# UNO-TH_Rev3e.net
KiCad netlist of a schematic drawn in Altium Designer
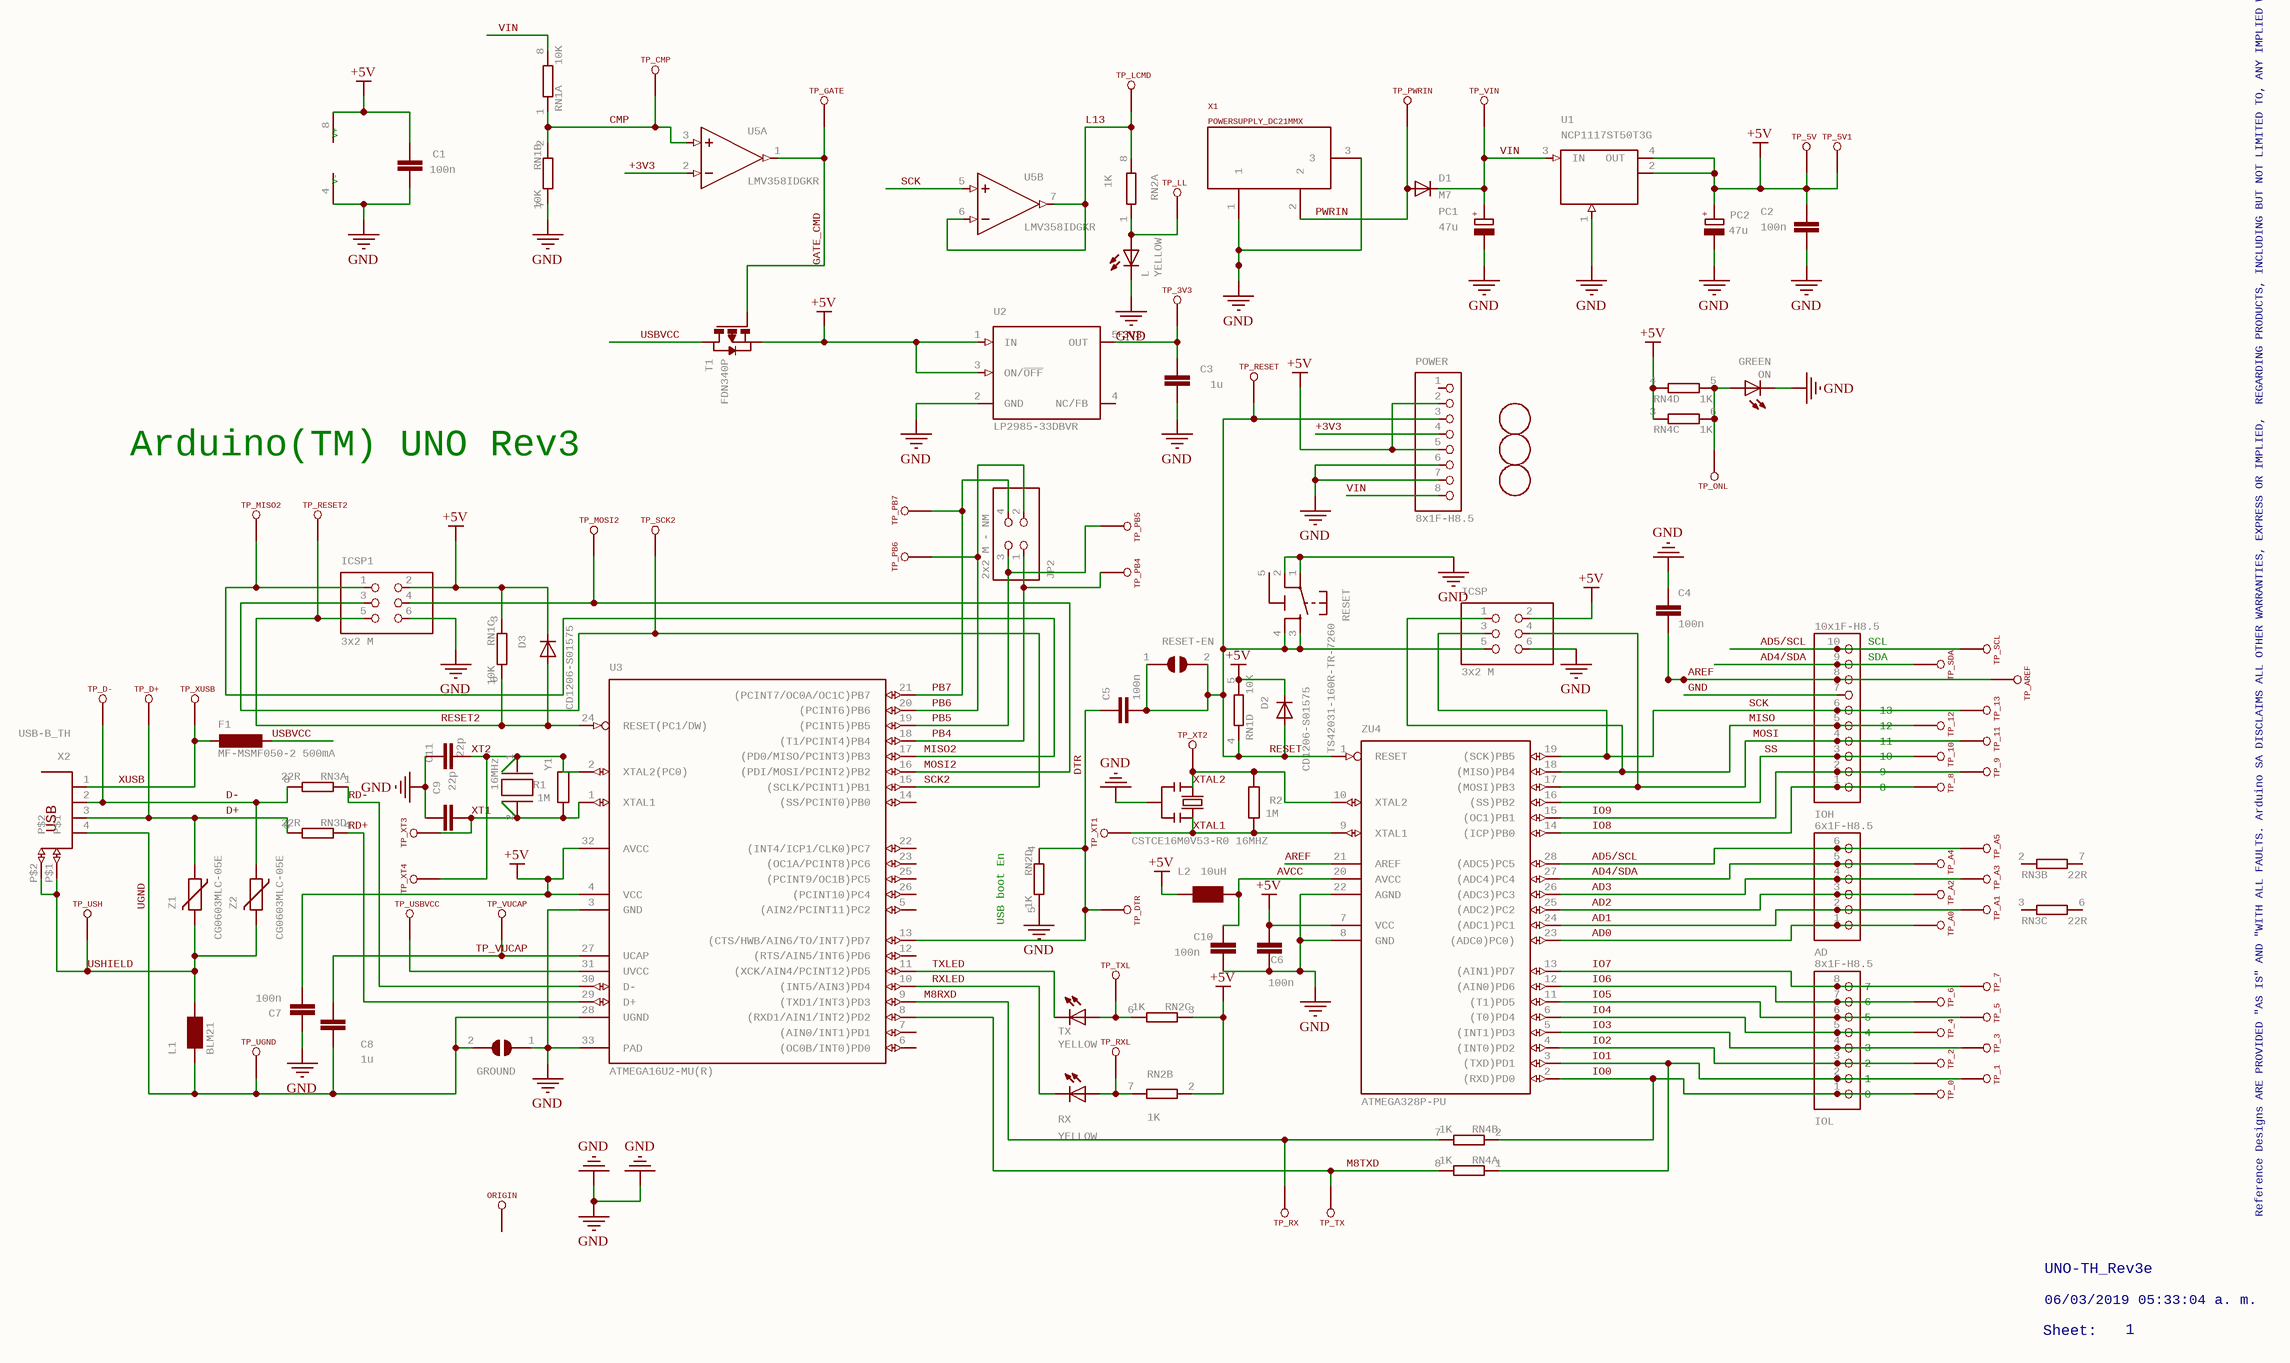
[diagram p0: UNO-TH_Rev3e.SchDoc]

(export (version "E")
  (design (tool "Eeschema 10.0.6"))
  (components
    (comp (ref "AD")
      (value "6x1F-H8.5")
      (footprint "1X06")
      (description "PIN HEADER")
      (libsource (lib "SmartPrj") (part "PINHD-1X6"))
    )
    (comp (ref "C1")
      (value "100n")
      (footprint "C0603-ROUND")
      (description "CAPACITOR, European symbol")
      (libsource (lib "") (part "C-EU0603-RND_1"))
    )
    (comp (ref "C2")
      (value "100n")
      (footprint "C0603-ROUND")
      (description "CAPACITOR, European symbol")
      (libsource (lib "") (part "C-EU0603-RND_3"))
    )
    (comp (ref "C3")
      (value "1u")
      (footprint "C0603-ROUND")
      (description "CAPACITOR, European symbol")
      (libsource (lib "") (part "C-EU0603-RND_1"))
    )
    (comp (ref "C4")
      (value "100n")
      (footprint "C0603-ROUND")
      (description "CAPACITOR, European symbol")
      (libsource (lib "") (part "C-EU0603-RND_2"))
    )
    (comp (ref "C5")
      (value "100n")
      (footprint "C0603-ROUND")
      (description "CAPACITOR, European symbol")
      (libsource (lib "") (part "C-EU0603-RND_1"))
    )
    (comp (ref "C6")
      (value "100n")
      (footprint "C0603-ROUND")
      (description "CAPACITOR, European symbol")
      (libsource (lib "") (part "C-EU0603-RND_3"))
    )
    (comp (ref "C7")
      (value "100n")
      (footprint "C0603-ROUND")
      (description "CAPACITOR, European symbol")
      (libsource (lib "SmartPrj") (part "C-EU0603-RND"))
    )
    (comp (ref "C8")
      (value "1u")
      (footprint "C0603-ROUND")
      (description "CAPACITOR, European symbol")
      (libsource (lib "SmartPrj") (part "C-EU0603-RND"))
    )
    (comp (ref "C9")
      (value "22p")
      (footprint "C0603-ROUND")
      (description "CAPACITOR, European symbol")
      (libsource (lib "") (part "C-EU0603-RND_2"))
    )
    (comp (ref "C10")
      (value "100n")
      (footprint "C0603-ROUND")
      (description "CAPACITOR, European symbol")
      (libsource (lib "") (part "C-EU0603-RND_3"))
    )
    (comp (ref "C11")
      (value "22p")
      (footprint "C0603-ROUND")
      (description "CAPACITOR, European symbol")
      (libsource (lib "") (part "C-EU0603-RND_2"))
    )
    (comp (ref "D1")
      (value "M7")
      (footprint "SMB")
      (description "DIODE")
      (libsource (lib "diode") (part "DIODE-SMB"))
    )
    (comp (ref "D2")
      (value "CD1206-S01575")
      (footprint "MINIMELF")
      (description "DIODE")
      (libsource (lib "diode") (part "DIODE-MINIMELF"))
    )
    (comp (ref "D3")
      (value "CD1206-S01575")
      (footprint "MINIMELF")
      (description "DIODE")
      (libsource (lib "diode") (part "DIODE-MINIMELF"))
    )
    (comp (ref "F1")
      (value "MF-MSMF050-2 500mA")
      (footprint "L1812")
      (description "INDUCTOR, European symbol")
      (libsource (lib "rcl") (part "L-EUL1812"))
    )
    (comp (ref "FD1")
      (value "FIDUCIALMOUNT")
      (footprint "FIDUCIA-MOUNT")
      (libsource (lib "SmartPrj") (part "FIDUCIALMOUNT"))
    )
    (comp (ref "FD2")
      (value "FIDUCIALMOUNT")
      (footprint "FIDUCIA-MOUNT")
      (libsource (lib "SmartPrj") (part "FIDUCIALMOUNT"))
    )
    (comp (ref "FD3")
      (value "FIDUCIALMOUNT")
      (footprint "FIDUCIA-MOUNT")
      (libsource (lib "SmartPrj") (part "FIDUCIALMOUNT"))
    )
    (comp (ref "GROUND")
      (value "SJ")
      (footprint "SJ")
      (description "SMD solder JUMPER")
      (libsource (lib "jumper") (part "SJ"))
    )
    (comp (ref "ICSP")
      (value "3x2 M")
      (footprint "2X03")
      (description "PIN HEADER")
      (libsource (lib "SmartPrj") (part "PINHD-2X3"))
    )
    (comp (ref "ICSP1")
      (value "3x2 M")
      (footprint "2X03")
      (description "PIN HEADER")
      (libsource (lib "SmartPrj") (part "PINHD-2X3"))
    )
    (comp (ref "IOH")
      (value "10x1F-H8.5")
      (footprint "1X10")
      (description "PIN HEADER")
      (libsource (lib "SmartPrj") (part "PINHD-1X10_ARD"))
    )
    (comp (ref "IOL")
      (value "8x1F-H8.5")
      (footprint "1X08")
      (description "PIN HEADER")
      (libsource (lib "SmartPrj") (part "PINHD-1X8"))
    )
    (comp (ref "JP2")
      (value "2x2 M - NM")
      (footprint "2X02")
      (description "PIN HEADER")
      (libsource (lib "SmartPrj") (part "PINHD-2X2"))
    )
    (comp (ref "L")
      (value "YELLOW")
      (footprint "CHIP-LED0805")
      (libsource (lib "led") (part "LEDCHIP-LED0805"))
    )
    (comp (ref "L1")
      (value "BLM21")
      (footprint "0805")
      (libsource (lib "wuerth-elektronik") (part "WE-CBF_0805"))
    )
    (comp (ref "L2")
      (value "10uH")
      (footprint "0805")
      (description "10uH 0805")
      (fields (field (name "PART_NUMBER") "CV201210-100K"))
      (libsource (lib "Induttanze") (part "0715_CV201210-100K"))
    )
    (comp (ref "ON")
      (value "GREEN")
      (footprint "CHIP-LED0805")
      (libsource (lib "led") (part "LEDCHIP-LED0805"))
    )
    (comp (ref "ORIGIN") (value "TP_SP") (footprint "TP-SP") (libsource (lib "SmartPrj") (part "TP_SP")))
    (comp (ref "PC1")
      (value "47u")
      (footprint "PANASONIC_D")
      (description "POLARIZED CAPACITOR, European symbol")
      (fields (field (name "+") "+"))
      (libsource (lib "rcl") (part "CPOL-EUD"))
    )
    (comp (ref "PC2")
      (value "47u")
      (footprint "PANASONIC_D")
      (description "POLARIZED CAPACITOR, European symbol")
      (fields (field (name "+") "+"))
      (libsource (lib "rcl") (part "CPOL-EUD"))
    )
    (comp (ref "POWER")
      (value "8x1F-H8.5")
      (footprint "1X08")
      (description "PIN HEADER")
      (libsource (lib "SmartPrj") (part "PINHD-1X8"))
    )
    (comp (ref "R1")
      (value "1M")
      (footprint "R0603-ROUND")
      (description "RESISTOR, European symbol")
      (libsource (lib "SmartPrj") (part "R-EU_R0603"))
    )
    (comp (ref "R2")
      (value "1M")
      (footprint "R0603-ROUND")
      (description "RESISTOR, European symbol")
      (libsource (lib "SmartPrj") (part "R-EU_R0603"))
    )
    (comp (ref "RESET")
      (value "TS42031-160R-TR-7260")
      (footprint "TS42")
      (description "TS42 Dongnan Electronics Tact switch VDC 12V - 50mA")
      (libsource (lib "SmartPrj") (part "TS42"))
    )
    (comp (ref "RESET-EN")
      (value "SJ")
      (footprint "SJ")
      (description "SMD solder JUMPER")
      (libsource (lib "jumper") (part "SJ"))
    )
    (comp (ref "RN1")
      (value "10K")
      (footprint "CAY16")
      (description "Array Chip Resistor   Source: RS Component / Phycomp")
      (libsource (lib "resistor-dil") (part "4R-NCAY16"))
    )
    (comp (ref "RN2")
      (value "1K")
      (footprint "CAY16")
      (description "Array Chip Resistor   Source: RS Component / Phycomp")
      (libsource (lib "resistor-dil") (part "4R-NCAY16"))
    )
    (comp (ref "RN3")
      (value "22R")
      (footprint "CAY16")
      (description "Array Chip Resistor   Source: RS Component / Phycomp")
      (libsource (lib "resistor-dil") (part "4R-NCAY16"))
    )
    (comp (ref "RN4")
      (value "1K")
      (footprint "CAY16")
      (description "Array Chip Resistor   Source: RS Component / Phycomp")
      (libsource (lib "resistor-dil") (part "4R-NCAY16"))
    )
    (comp (ref "RX")
      (value "YELLOW")
      (footprint "CHIP-LED0805")
      (libsource (lib "led") (part "LEDCHIP-LED0805"))
    )
    (comp (ref "T1")
      (value "FDN340P")
      (footprint "SOT-23")
      (description "MOS FET")
      (libsource (lib "zetex") (part "PMOSSOT23"))
    )
    (comp (ref "TP_0") (value "TP_SP") (footprint "TP-SP") (libsource (lib "SmartPrj") (part "TP_SP")))
    (comp (ref "TP_1") (value "TP_SP") (footprint "TP-SP") (libsource (lib "SmartPrj") (part "TP_SP")))
    (comp (ref "TP_2") (value "TP_SP") (footprint "TP-SP") (libsource (lib "SmartPrj") (part "TP_SP")))
    (comp (ref "TP_3") (value "TP_SP") (footprint "TP-SP") (libsource (lib "SmartPrj") (part "TP_SP")))
    (comp (ref "TP_3V3") (value "TP_SP") (footprint "TP-SP") (libsource (lib "SmartPrj") (part "TP_SP")))
    (comp (ref "TP_4") (value "TP_SP") (footprint "TP-SP") (libsource (lib "SmartPrj") (part "TP_SP")))
    (comp (ref "TP_5") (value "TP_SP") (footprint "TP-SP") (libsource (lib "SmartPrj") (part "TP_SP")))
    (comp (ref "TP_5V") (value "TP_SP") (footprint "TP-SP") (libsource (lib "SmartPrj") (part "TP_SP")))
    (comp (ref "TP_5V1") (value "TP_SP") (footprint "TP-SP") (libsource (lib "SmartPrj") (part "TP_SP")))
    (comp (ref "TP_6") (value "TP_SP") (footprint "TP-SP") (libsource (lib "SmartPrj") (part "TP_SP")))
    (comp (ref "TP_7") (value "TP_SP") (footprint "TP-SP") (libsource (lib "SmartPrj") (part "TP_SP")))
    (comp (ref "TP_8") (value "TP_SP") (footprint "TP-SP") (libsource (lib "SmartPrj") (part "TP_SP")))
    (comp (ref "TP_9") (value "TP_SP") (footprint "TP-SP") (libsource (lib "SmartPrj") (part "TP_SP")))
    (comp (ref "TP_10") (value "TP_SP") (footprint "TP-SP") (libsource (lib "SmartPrj") (part "TP_SP")))
    (comp (ref "TP_11") (value "TP_SP") (footprint "TP-SP") (libsource (lib "SmartPrj") (part "TP_SP")))
    (comp (ref "TP_12") (value "TP_SP") (footprint "TP-SP") (libsource (lib "SmartPrj") (part "TP_SP")))
    (comp (ref "TP_13") (value "TP_SP") (footprint "TP-SP") (libsource (lib "SmartPrj") (part "TP_SP")))
    (comp (ref "TP_A0") (value "TP_SP") (footprint "TP-SP") (libsource (lib "SmartPrj") (part "TP_SP")))
    (comp (ref "TP_A1") (value "TP_SP") (footprint "TP-SP") (libsource (lib "SmartPrj") (part "TP_SP")))
    (comp (ref "TP_A2") (value "TP_SP") (footprint "TP-SP") (libsource (lib "SmartPrj") (part "TP_SP")))
    (comp (ref "TP_A3") (value "TP_SP") (footprint "TP-SP") (libsource (lib "SmartPrj") (part "TP_SP")))
    (comp (ref "TP_A4") (value "TP_SP") (footprint "TP-SP") (libsource (lib "SmartPrj") (part "TP_SP")))
    (comp (ref "TP_A5") (value "TP_SP") (footprint "TP-SP") (libsource (lib "SmartPrj") (part "TP_SP")))
    (comp (ref "TP_AREF") (value "TP_SP") (footprint "TP-SP") (libsource (lib "SmartPrj") (part "TP_SP")))
    (comp (ref "TP_CMP") (value "TP_SP") (footprint "TP-SP") (libsource (lib "SmartPrj") (part "TP_SP")))
    (comp (ref "TP_D+") (value "TP_SP") (footprint "TP-SP") (libsource (lib "SmartPrj") (part "TP_SP")))
    (comp (ref "TP_D-") (value "TP_SP") (footprint "TP-SP") (libsource (lib "SmartPrj") (part "TP_SP")))
    (comp (ref "TP_DTR") (value "TP_SP") (footprint "TP-SP") (libsource (lib "SmartPrj") (part "TP_SP")))
    (comp (ref "TP_GATE") (value "TP_SP") (footprint "TP-SP") (libsource (lib "SmartPrj") (part "TP_SP")))
    (comp (ref "TP_LCMD") (value "TP_SP") (footprint "TP-SP") (libsource (lib "SmartPrj") (part "TP_SP")))
    (comp (ref "TP_LL") (value "TP_SP") (footprint "TP-SP") (libsource (lib "SmartPrj") (part "TP_SP")))
    (comp (ref "TP_MISO2") (value "TP_SP") (footprint "TP-SP") (libsource (lib "SmartPrj") (part "TP_SP")))
    (comp (ref "TP_MOSI2") (value "TP_SP") (footprint "TP-SP") (libsource (lib "SmartPrj") (part "TP_SP")))
    (comp (ref "TP_ONL") (value "TP_SP") (footprint "TP-SP") (libsource (lib "SmartPrj") (part "TP_SP")))
    (comp (ref "TP_PB4") (value "TP_SP") (footprint "TP-SP") (libsource (lib "SmartPrj") (part "TP_SP")))
    (comp (ref "TP_PB5") (value "TP_SP") (footprint "TP-SP") (libsource (lib "SmartPrj") (part "TP_SP")))
    (comp (ref "TP_PB6") (value "TP_SP") (footprint "TP-SP") (libsource (lib "SmartPrj") (part "TP_SP")))
    (comp (ref "TP_PB7") (value "TP_SP") (footprint "TP-SP") (libsource (lib "SmartPrj") (part "TP_SP")))
    (comp (ref "TP_PWRIN") (value "TP_SP") (footprint "TP-SP") (libsource (lib "SmartPrj") (part "TP_SP")))
    (comp (ref "TP_RESET") (value "TP_SP") (footprint "TP-SP") (libsource (lib "SmartPrj") (part "TP_SP")))
    (comp (ref "TP_RESET2") (value "TP_SP") (footprint "TP-SP") (libsource (lib "SmartPrj") (part "TP_SP")))
    (comp (ref "TP_RX") (value "TP_SP") (footprint "TP-SP") (libsource (lib "SmartPrj") (part "TP_SP")))
    (comp (ref "TP_RXL") (value "TP_SP") (footprint "TP-SP") (libsource (lib "SmartPrj") (part "TP_SP")))
    (comp (ref "TP_SCK2") (value "TP_SP") (footprint "TP-SP") (libsource (lib "SmartPrj") (part "TP_SP")))
    (comp (ref "TP_SCL") (value "TP_SP") (footprint "TP-SP") (libsource (lib "SmartPrj") (part "TP_SP")))
    (comp (ref "TP_SDA") (value "TP_SP") (footprint "TP-SP") (libsource (lib "SmartPrj") (part "TP_SP")))
    (comp (ref "TP_TX") (value "TP_SP") (footprint "TP-SP") (libsource (lib "SmartPrj") (part "TP_SP")))
    (comp (ref "TP_TXL") (value "TP_SP") (footprint "TP-SP") (libsource (lib "SmartPrj") (part "TP_SP")))
    (comp (ref "TP_UGND") (value "TP_SP") (footprint "TP-SP") (libsource (lib "SmartPrj") (part "TP_SP")))
    (comp (ref "TP_USBVCC") (value "TP_SP") (footprint "TP-SP") (libsource (lib "SmartPrj") (part "TP_SP")))
    (comp (ref "TP_USH") (value "TP_SP") (footprint "TP-SP") (libsource (lib "SmartPrj") (part "TP_SP")))
    (comp (ref "TP_VIN") (value "TP_SP") (footprint "TP-SP") (libsource (lib "SmartPrj") (part "TP_SP")))
    (comp (ref "TP_VUCAP") (value "TP_SP") (footprint "TP-SP") (libsource (lib "SmartPrj") (part "TP_SP")))
    (comp (ref "TP_XT1") (value "TP_SP") (footprint "TP-SP") (libsource (lib "SmartPrj") (part "TP_SP")))
    (comp (ref "TP_XT2") (value "TP_SP") (footprint "TP-SP") (libsource (lib "SmartPrj") (part "TP_SP")))
    (comp (ref "TP_XT3") (value "TP_SP") (footprint "TP-SP") (libsource (lib "SmartPrj") (part "TP_SP")))
    (comp (ref "TP_XT4") (value "TP_SP") (footprint "TP-SP") (libsource (lib "SmartPrj") (part "TP_SP")))
    (comp (ref "TP_XUSB") (value "TP_SP") (footprint "TP-SP") (libsource (lib "SmartPrj") (part "TP_SP")))
    (comp (ref "TX")
      (value "YELLOW")
      (footprint "CHIP-LED0805")
      (libsource (lib "led") (part "LEDCHIP-LED0805"))
    )
    (comp (ref "U1")
      (value "NCP1117ST50T3G")
      (footprint "SOT223")
      (libsource (lib "linear") (part "MC33269ST*"))
    )
    (comp (ref "U2")
      (value "LP2985-33DBVR")
      (footprint "SOT23-DBV")
      (libsource (lib "SmartPrj") (part "LP2985-XXDBVR"))
    )
    (comp (ref "U3")
      (value "ATMEGA16U2-MU(R)")
      (footprint "MLF32")
      (libsource (lib "SmartPrj") (part "ATMEGA16U2-MU"))
    )
    (comp (ref "U5")
      (value "LMV358IDGKR")
      (footprint "MSOP08")
      (fields (field (name "V+") "V+") (field (name "V-") "V-"))
      (libsource (lib "linear") (part "LMV358?*MM"))
    )
    (comp (ref "X1")
      (value "POWERSUPPLY_DC21MMX")
      (footprint "POWERSUPPLY_DC-21MM")
      (libsource (lib "SmartPrj") (part "POWERSUPPLY_DC21MMX"))
    )
    (comp (ref "X2")
      (value "USB-B_TH")
      (footprint "PN61729")
      (description "BERG USB connector")
      (fields (field (name "USB") "USB"))
      (libsource (lib "SmartPrj") (part "PN61729"))
    )
    (comp (ref "Y1")
      (value "16MHz")
      (footprint "QS")
      (description "CRYSTAL")
      (libsource (lib "SmartPrj") (part "XTAL/S"))
    )
    (comp (ref "Y2")
      (value "CSTCE16M0V53-R0 16MHZ")
      (footprint "RESONATOR")
      (libsource (lib "SmartPrj") (part "RESONATORMU"))
    )
    (comp (ref "Z1")
      (value "CG0603MLC-05E")
      (footprint "CT/CN0603")
      (description "VARISTOR")
      (libsource (lib "varistor") (part "VARISTORCN0603"))
    )
    (comp (ref "Z2")
      (value "CG0603MLC-05E")
      (footprint "CT/CN0603")
      (description "VARISTOR")
      (libsource (lib "varistor") (part "VARISTORCN0603"))
    )
    (comp (ref "ZU4")
      (value "ATMEGA328P-PU")
      (footprint "DIL28-3")
      (description "MICROCONTROLLER   4 Kbytes FLASH   128 bytes SRAM   256 bytes EEPROM   UART   6-channel 10 bit ADC")
      (libsource (lib "SmartPrj") (part "ATMEGA328P-PU"))
    )
  )
  (nets
    (net (code "1") (name "+5V") (class "Default")
      (node (ref "C1") (pin "2") (pinfunction "2_2") (pintype "passive"))
      (node (ref "C2") (pin "2") (pinfunction "2_2") (pintype "passive"))
      (node (ref "C6") (pin "2") (pinfunction "2_2") (pintype "passive"))
      (node (ref "C7") (pin "1") (pinfunction "1_1") (pintype "passive"))
      (node (ref "D2") (pin "C") (pinfunction "C_C") (pintype "passive"))
      (node (ref "D3") (pin "C") (pinfunction "C_C") (pintype "passive"))
      (node (ref "ICSP") (pin "2") (pinfunction "2_2") (pintype "passive"))
      (node (ref "ICSP1") (pin "2") (pinfunction "2_2") (pintype "passive"))
      (node (ref "L2") (pin "1") (pinfunction "1_1") (pintype "passive"))
      (node (ref "PC2") (pin "+") (pinfunction "+_+") (pintype "passive"))
      (node (ref "POWER") (pin "2") (pinfunction "2_2") (pintype "passive"))
      (node (ref "POWER") (pin "5") (pinfunction "5_5") (pintype "passive"))
      (node (ref "RN1") (pin "3") (pinfunction "1_3") (pintype "passive"))
      (node (ref "RN1") (pin "5") (pinfunction "2_5") (pintype "passive"))
      (node (ref "RN2") (pin "2") (pinfunction "1_2") (pintype "passive"))
      (node (ref "RN2") (pin "3") (pinfunction "1_3") (pintype "passive"))
      (node (ref "RN4") (pin "3") (pinfunction "1_3") (pintype "passive"))
      (node (ref "RN4") (pin "4") (pinfunction "1_4") (pintype "passive"))
      (node (ref "T1") (pin "2") (pinfunction "S_2") (pintype "passive"))
      (node (ref "TP_5V") (pin "X") (pinfunction "TESTP_X") (pintype "passive"))
      (node (ref "TP_5V1") (pin "X") (pinfunction "TESTP_X") (pintype "passive"))
      (node (ref "U1") (pin "2") (pinfunction "OUT_2") (pintype "passive"))
      (node (ref "U1") (pin "4") (pinfunction "OUT_4") (pintype "passive"))
      (node (ref "U2") (pin "1") (pinfunction "IN_1") (pintype "input"))
      (node (ref "U2") (pin "3") (pinfunction "ON/~{OFF}_3") (pintype "input"))
      (node (ref "U3") (pin "32") (pinfunction "AVCC_32") (pintype "power_in"))
      (node (ref "U3") (pin "4") (pinfunction "VCC_4") (pintype "power_in"))
      (node (ref "U5") (pin "8") (pinfunction "V+_8") (pintype "power_in"))
      (node (ref "ZU4") (pin "7") (pinfunction "VCC_7") (pintype "power_in"))
    )
    (net (code "2") (name "/+3V3") (class "Default")
      (node (ref "C3") (pin "2") (pinfunction "2_2") (pintype "passive"))
      (node (ref "POWER") (pin "4") (pinfunction "4_4") (pintype "passive"))
      (node (ref "TP_3V3") (pin "X") (pinfunction "TESTP_X") (pintype "passive"))
      (node (ref "U2") (pin "5") (pinfunction "OUT_5") (pintype "passive"))
      (node (ref "U5") (pin "2") (pinfunction "-IN_2") (pintype "input"))
    )
    (net (code "3") (name "/AD0") (class "Default")
      (node (ref "AD") (pin "1") (pinfunction "1_1") (pintype "passive"))
      (node (ref "TP_A0") (pin "X") (pinfunction "TESTP_X") (pintype "passive"))
      (node (ref "ZU4") (pin "23") (pinfunction "(ADC0)PC0)_23") (pintype "bidirectional"))
    )
    (net (code "4") (name "/AD1") (class "Default")
      (node (ref "AD") (pin "2") (pinfunction "2_2") (pintype "passive"))
      (node (ref "TP_A1") (pin "X") (pinfunction "TESTP_X") (pintype "passive"))
      (node (ref "ZU4") (pin "24") (pinfunction "(ADC1)PC1_24") (pintype "bidirectional"))
    )
    (net (code "5") (name "/AD2") (class "Default")
      (node (ref "AD") (pin "3") (pinfunction "3_3") (pintype "passive"))
      (node (ref "TP_A2") (pin "X") (pinfunction "TESTP_X") (pintype "passive"))
      (node (ref "ZU4") (pin "25") (pinfunction "(ADC2)PC2_25") (pintype "bidirectional"))
    )
    (net (code "6") (name "/AD3") (class "Default")
      (node (ref "AD") (pin "4") (pinfunction "4_4") (pintype "passive"))
      (node (ref "TP_A3") (pin "X") (pinfunction "TESTP_X") (pintype "passive"))
      (node (ref "ZU4") (pin "26") (pinfunction "(ADC3)PC3_26") (pintype "bidirectional"))
    )
    (net (code "7") (name "/AD4{slash}SDA") (class "Default")
      (node (ref "AD") (pin "5") (pinfunction "5_5") (pintype "passive"))
      (node (ref "IOH") (pin "9") (pinfunction "9_9") (pintype "passive"))
      (node (ref "TP_A4") (pin "X") (pinfunction "TESTP_X") (pintype "passive"))
      (node (ref "TP_SDA") (pin "X") (pinfunction "TESTP_X") (pintype "passive"))
      (node (ref "ZU4") (pin "27") (pinfunction "(ADC4)PC4_27") (pintype "bidirectional"))
    )
    (net (code "8") (name "/AD5{slash}SCL") (class "Default")
      (node (ref "AD") (pin "6") (pinfunction "6_6") (pintype "passive"))
      (node (ref "IOH") (pin "10") (pinfunction "10_10") (pintype "passive"))
      (node (ref "TP_A5") (pin "X") (pinfunction "TESTP_X") (pintype "passive"))
      (node (ref "TP_SCL") (pin "X") (pinfunction "TESTP_X") (pintype "passive"))
      (node (ref "ZU4") (pin "28") (pinfunction "(ADC5)PC5_28") (pintype "bidirectional"))
    )
    (net (code "9") (name "/AREF") (class "Default")
      (node (ref "C4") (pin "2") (pinfunction "2_2") (pintype "passive"))
      (node (ref "IOH") (pin "8") (pinfunction "8_8") (pintype "passive"))
      (node (ref "TP_AREF") (pin "X") (pinfunction "TESTP_X") (pintype "passive"))
      (node (ref "ZU4") (pin "21") (pinfunction "AREF_21") (pintype "passive"))
    )
    (net (code "10") (name "/AVCC") (class "Default")
      (node (ref "C10") (pin "2") (pinfunction "2_2") (pintype "passive"))
      (node (ref "L2") (pin "2") (pinfunction "2_2") (pintype "passive"))
      (node (ref "ZU4") (pin "20") (pinfunction "AVCC_20") (pintype "power_in"))
    )
    (net (code "11") (name "/CMP") (class "Default")
      (node (ref "RN1") (pin "1") (pinfunction "1_1") (pintype "passive"))
      (node (ref "RN1") (pin "2") (pinfunction "1_2") (pintype "passive"))
      (node (ref "TP_CMP") (pin "X") (pinfunction "TESTP_X") (pintype "passive"))
      (node (ref "U5") (pin "3") (pinfunction "+IN_3") (pintype "input"))
    )
    (net (code "12") (name "/D+") (class "Default")
      (node (ref "RN3") (pin "5") (pinfunction "2_5") (pintype "passive"))
      (node (ref "TP_D+") (pin "X") (pinfunction "TESTP_X") (pintype "passive"))
      (node (ref "X2") (pin "3") (pinfunction "3_3") (pintype "bidirectional"))
      (node (ref "Z1") (pin "1") (pinfunction "1_1") (pintype "passive"))
    )
    (net (code "13") (name "/D-") (class "Default")
      (node (ref "RN3") (pin "8") (pinfunction "2_8") (pintype "passive"))
      (node (ref "TP_D-") (pin "X") (pinfunction "TESTP_X") (pintype "passive"))
      (node (ref "X2") (pin "2") (pinfunction "2_2") (pintype "bidirectional"))
      (node (ref "Z2") (pin "1") (pinfunction "1_1") (pintype "passive"))
    )
    (net (code "14") (name "/DTR") (class "Default")
      (node (ref "C5") (pin "1") (pinfunction "1_1") (pintype "passive"))
      (node (ref "RN2") (pin "4") (pinfunction "1_4") (pintype "passive"))
      (node (ref "TP_DTR") (pin "X") (pinfunction "TESTP_X") (pintype "passive"))
      (node (ref "U3") (pin "13") (pinfunction "(CTS/HWB/AIN6/TO/INT7)PD7_13") (pintype "bidirectional"))
    )
    (net (code "15") (name "/GATE_CMD") (class "Default")
      (node (ref "T1") (pin "3") (pinfunction "G_3") (pintype "passive"))
      (node (ref "TP_GATE") (pin "X") (pinfunction "TESTP_X") (pintype "passive"))
      (node (ref "U5") (pin "1") (pinfunction "OUT_1") (pintype "output"))
    )
    (net (code "16") (name "/IO0") (class "Default")
      (node (ref "IOL") (pin "1") (pinfunction "1_1") (pintype "passive"))
      (node (ref "RN4") (pin "2") (pinfunction "1_2") (pintype "passive"))
      (node (ref "TP_0") (pin "X") (pinfunction "TESTP_X") (pintype "passive"))
      (node (ref "ZU4") (pin "2") (pinfunction "(RXD)PD0_2") (pintype "bidirectional"))
    )
    (net (code "17") (name "/IO1") (class "Default")
      (node (ref "IOL") (pin "2") (pinfunction "2_2") (pintype "passive"))
      (node (ref "RN4") (pin "1") (pinfunction "1_1") (pintype "passive"))
      (node (ref "TP_1") (pin "X") (pinfunction "TESTP_X") (pintype "passive"))
      (node (ref "ZU4") (pin "3") (pinfunction "(TXD)PD1_3") (pintype "bidirectional"))
    )
    (net (code "18") (name "/IO2") (class "Default")
      (node (ref "IOL") (pin "3") (pinfunction "3_3") (pintype "passive"))
      (node (ref "TP_2") (pin "X") (pinfunction "TESTP_X") (pintype "passive"))
      (node (ref "ZU4") (pin "4") (pinfunction "(INT0)PD2_4") (pintype "bidirectional"))
    )
    (net (code "19") (name "/IO3") (class "Default")
      (node (ref "IOL") (pin "4") (pinfunction "4_4") (pintype "passive"))
      (node (ref "TP_3") (pin "X") (pinfunction "TESTP_X") (pintype "passive"))
      (node (ref "ZU4") (pin "5") (pinfunction "(INT1)PD3_5") (pintype "bidirectional"))
    )
    (net (code "20") (name "/IO4") (class "Default")
      (node (ref "IOL") (pin "5") (pinfunction "5_5") (pintype "passive"))
      (node (ref "TP_4") (pin "X") (pinfunction "TESTP_X") (pintype "passive"))
      (node (ref "ZU4") (pin "6") (pinfunction "(T0)PD4_6") (pintype "bidirectional"))
    )
    (net (code "21") (name "/IO5") (class "Default")
      (node (ref "IOL") (pin "6") (pinfunction "6_6") (pintype "passive"))
      (node (ref "TP_5") (pin "X") (pinfunction "TESTP_X") (pintype "passive"))
      (node (ref "ZU4") (pin "11") (pinfunction "(T1)PD5_11") (pintype "bidirectional"))
    )
    (net (code "22") (name "/IO6") (class "Default")
      (node (ref "IOL") (pin "7") (pinfunction "7_7") (pintype "passive"))
      (node (ref "TP_6") (pin "X") (pinfunction "TESTP_X") (pintype "passive"))
      (node (ref "ZU4") (pin "12") (pinfunction "(AIN0)PD6_12") (pintype "bidirectional"))
    )
    (net (code "23") (name "/IO7") (class "Default")
      (node (ref "IOL") (pin "8") (pinfunction "8_8") (pintype "passive"))
      (node (ref "TP_7") (pin "X") (pinfunction "TESTP_X") (pintype "passive"))
      (node (ref "ZU4") (pin "13") (pinfunction "(AIN1)PD7_13") (pintype "bidirectional"))
    )
    (net (code "24") (name "/IO8") (class "Default")
      (node (ref "IOH") (pin "1") (pinfunction "1_1") (pintype "passive"))
      (node (ref "TP_8") (pin "X") (pinfunction "TESTP_X") (pintype "passive"))
      (node (ref "ZU4") (pin "14") (pinfunction "(ICP)PB0_14") (pintype "bidirectional"))
    )
    (net (code "25") (name "/IO9") (class "Default")
      (node (ref "IOH") (pin "2") (pinfunction "2_2") (pintype "passive"))
      (node (ref "TP_9") (pin "X") (pinfunction "TESTP_X") (pintype "passive"))
      (node (ref "ZU4") (pin "15") (pinfunction "(OC1)PB1_15") (pintype "bidirectional"))
    )
    (net (code "26") (name "/L13") (class "Default")
      (node (ref "RN2") (pin "8") (pinfunction "2_8") (pintype "passive"))
      (node (ref "TP_LCMD") (pin "X") (pinfunction "TESTP_X") (pintype "passive"))
      (node (ref "U5") (pin "6") (pinfunction "-IN_6") (pintype "input"))
      (node (ref "U5") (pin "7") (pinfunction "OUT_7") (pintype "output"))
    )
    (net (code "27") (name "/M8RXD") (class "Default")
      (node (ref "RN4") (pin "7") (pinfunction "2_7") (pintype "passive"))
      (node (ref "TP_RX") (pin "X") (pinfunction "TESTP_X") (pintype "passive"))
      (node (ref "U3") (pin "9") (pinfunction "(TXD1/INT3)PD3_9") (pintype "bidirectional"))
    )
    (net (code "28") (name "/M8TXD") (class "Default")
      (node (ref "RN4") (pin "8") (pinfunction "2_8") (pintype "passive"))
      (node (ref "TP_TX") (pin "X") (pinfunction "TESTP_X") (pintype "passive"))
      (node (ref "U3") (pin "8") (pinfunction "(RXD1/AIN1/INT2)PD2_8") (pintype "bidirectional"))
    )
    (net (code "29") (name "/MISO") (class "Default")
      (node (ref "ICSP") (pin "1") (pinfunction "1_1") (pintype "passive"))
      (node (ref "IOH") (pin "5") (pinfunction "5_5") (pintype "passive"))
      (node (ref "TP_12") (pin "X") (pinfunction "TESTP_X") (pintype "passive"))
      (node (ref "ZU4") (pin "18") (pinfunction "(MISO)PB4_18") (pintype "bidirectional"))
    )
    (net (code "30") (name "/MISO2") (class "Default")
      (node (ref "ICSP1") (pin "1") (pinfunction "1_1") (pintype "passive"))
      (node (ref "TP_MISO2") (pin "X") (pinfunction "TESTP_X") (pintype "passive"))
      (node (ref "U3") (pin "17") (pinfunction "(PD0/MISO/PCINT3)PB3_17") (pintype "bidirectional"))
    )
    (net (code "31") (name "/MOSI") (class "Default")
      (node (ref "ICSP") (pin "4") (pinfunction "4_4") (pintype "passive"))
      (node (ref "IOH") (pin "4") (pinfunction "4_4") (pintype "passive"))
      (node (ref "TP_11") (pin "X") (pinfunction "TESTP_X") (pintype "passive"))
      (node (ref "ZU4") (pin "17") (pinfunction "(MOSI)PB3_17") (pintype "bidirectional"))
    )
    (net (code "32") (name "/MOSI2") (class "Default")
      (node (ref "ICSP1") (pin "4") (pinfunction "4_4") (pintype "passive"))
      (node (ref "TP_MOSI2") (pin "X") (pinfunction "TESTP_X") (pintype "passive"))
      (node (ref "U3") (pin "16") (pinfunction "(PDI/MOSI/PCINT2)PB2_16") (pintype "bidirectional"))
    )
    (net (code "33") (name "/PB4") (class "Default")
      (node (ref "JP2") (pin "1") (pinfunction "1_1") (pintype "passive"))
      (node (ref "TP_PB4") (pin "X") (pinfunction "TESTP_X") (pintype "passive"))
      (node (ref "U3") (pin "18") (pinfunction "(T1/PCINT4)PB4_18") (pintype "bidirectional"))
    )
    (net (code "34") (name "/PB5") (class "Default")
      (node (ref "JP2") (pin "3") (pinfunction "3_3") (pintype "passive"))
      (node (ref "TP_PB5") (pin "X") (pinfunction "TESTP_X") (pintype "passive"))
      (node (ref "U3") (pin "19") (pinfunction "(PCINT5)PB5_19") (pintype "bidirectional"))
    )
    (net (code "35") (name "/PB6") (class "Default")
      (node (ref "JP2") (pin "2") (pinfunction "2_2") (pintype "passive"))
      (node (ref "TP_PB6") (pin "X") (pinfunction "TESTP_X") (pintype "passive"))
      (node (ref "U3") (pin "20") (pinfunction "(PCINT6)PB6_20") (pintype "bidirectional"))
    )
    (net (code "36") (name "/PB7") (class "Default")
      (node (ref "JP2") (pin "4") (pinfunction "4_4") (pintype "passive"))
      (node (ref "TP_PB7") (pin "X") (pinfunction "TESTP_X") (pintype "passive"))
      (node (ref "U3") (pin "21") (pinfunction "(PCINT7/OC0A/OC1C)PB7_21") (pintype "bidirectional"))
    )
    (net (code "37") (name "/PWRIN") (class "Default")
      (node (ref "D1") (pin "A") (pinfunction "A_A") (pintype "passive"))
      (node (ref "TP_PWRIN") (pin "X") (pinfunction "TESTP_X") (pintype "passive"))
      (node (ref "X1") (pin "2") (pinfunction "2_2") (pintype "power_in"))
    )
    (net (code "38") (name "/RD+") (class "Default")
      (node (ref "RN3") (pin "4") (pinfunction "1_4") (pintype "passive"))
      (node (ref "U3") (pin "29") (pinfunction "D+_29") (pintype "bidirectional"))
    )
    (net (code "39") (name "/RD-") (class "Default")
      (node (ref "RN3") (pin "1") (pinfunction "1_1") (pintype "passive"))
      (node (ref "U3") (pin "30") (pinfunction "D-_30") (pintype "bidirectional"))
    )
    (net (code "40") (name "/RESET") (class "Default")
      (node (ref "C5") (pin "2") (pinfunction "2_2") (pintype "passive"))
      (node (ref "D2") (pin "A") (pinfunction "A_A") (pintype "passive"))
      (node (ref "ICSP") (pin "5") (pinfunction "5_5") (pintype "passive"))
      (node (ref "POWER") (pin "3") (pinfunction "3_3") (pintype "passive"))
      (node (ref "RESET") (pin "3") (pinfunction "3_3") (pintype "passive"))
      (node (ref "RESET") (pin "4") (pinfunction "4_4") (pintype "passive"))
      (node (ref "RESET-EN") (pin "1") (pinfunction "1_1") (pintype "passive"))
      (node (ref "RESET-EN") (pin "2") (pinfunction "2_2") (pintype "passive"))
      (node (ref "RN1") (pin "4") (pinfunction "1_4") (pintype "passive"))
      (node (ref "TP_RESET") (pin "X") (pinfunction "TESTP_X") (pintype "passive"))
      (node (ref "ZU4") (pin "1") (pinfunction "RESET_1") (pintype "input"))
    )
    (net (code "41") (name "/RESET2") (class "Default")
      (node (ref "D3") (pin "A") (pinfunction "A_A") (pintype "passive"))
      (node (ref "ICSP1") (pin "5") (pinfunction "5_5") (pintype "passive"))
      (node (ref "RN1") (pin "6") (pinfunction "2_6") (pintype "passive"))
      (node (ref "TP_RESET2") (pin "X") (pinfunction "TESTP_X") (pintype "passive"))
      (node (ref "U3") (pin "24") (pinfunction "RESET(PC1/DW)_24") (pintype "input"))
    )
    (net (code "42") (name "/RXLED") (class "Default")
      (node (ref "RX") (pin "C") (pinfunction "C_C") (pintype "passive"))
      (node (ref "U3") (pin "10") (pinfunction "(INT5/AIN3)PD4_10") (pintype "bidirectional"))
    )
    (net (code "43") (name "/SCK") (class "Default")
      (node (ref "ICSP") (pin "3") (pinfunction "3_3") (pintype "passive"))
      (node (ref "IOH") (pin "6") (pinfunction "6_6") (pintype "passive"))
      (node (ref "TP_13") (pin "X") (pinfunction "TESTP_X") (pintype "passive"))
      (node (ref "U5") (pin "5") (pinfunction "+IN_5") (pintype "input"))
      (node (ref "ZU4") (pin "19") (pinfunction "(SCK)PB5_19") (pintype "bidirectional"))
    )
    (net (code "44") (name "/SCK2") (class "Default")
      (node (ref "ICSP1") (pin "3") (pinfunction "3_3") (pintype "passive"))
      (node (ref "TP_SCK2") (pin "X") (pinfunction "TESTP_X") (pintype "passive"))
      (node (ref "U3") (pin "15") (pinfunction "(SCLK/PCINT1)PB1_15") (pintype "bidirectional"))
    )
    (net (code "45") (name "/SS") (class "Default")
      (node (ref "IOH") (pin "3") (pinfunction "3_3") (pintype "passive"))
      (node (ref "TP_10") (pin "X") (pinfunction "TESTP_X") (pintype "passive"))
      (node (ref "ZU4") (pin "16") (pinfunction "(SS)PB2_16") (pintype "bidirectional"))
    )
    (net (code "46") (name "/TP_VUCAP") (class "Default")
      (node (ref "C8") (pin "1") (pinfunction "1_1") (pintype "passive"))
      (node (ref "TP_VUCAP") (pin "X") (pinfunction "TESTP_X") (pintype "passive"))
      (node (ref "U3") (pin "27") (pinfunction "UCAP_27") (pintype "passive"))
    )
    (net (code "47") (name "/TXLED") (class "Default")
      (node (ref "TX") (pin "C") (pinfunction "C_C") (pintype "passive"))
      (node (ref "U3") (pin "11") (pinfunction "(XCK/AIN4/PCINT12)PD5_11") (pintype "bidirectional"))
    )
    (net (code "48") (name "/UGND") (class "Default")
      (node (ref "C8") (pin "2") (pinfunction "2_2") (pintype "passive"))
      (node (ref "GROUND") (pin "2") (pinfunction "2_2") (pintype "passive"))
      (node (ref "L1") (pin "1") (pinfunction "1_1") (pintype "passive"))
      (node (ref "TP_UGND") (pin "X") (pinfunction "TESTP_X") (pintype "passive"))
      (node (ref "U3") (pin "28") (pinfunction "UGND_28") (pintype "power_in"))
      (node (ref "X2") (pin "4") (pinfunction "4_4") (pintype "bidirectional"))
    )
    (net (code "49") (name "/USBVCC") (class "Default")
      (node (ref "F1") (pin "1") (pinfunction "1_1") (pintype "passive"))
      (node (ref "T1") (pin "1") (pinfunction "D_1") (pintype "passive"))
    )
    (net (code "50") (name "/USHIELD") (class "Default")
      (node (ref "L1") (pin "2") (pinfunction "2_2") (pintype "passive"))
      (node (ref "TP_USH") (pin "X") (pinfunction "TESTP_X") (pintype "passive"))
      (node (ref "X2") (pin "P$1") (pinfunction "P$1_P$1") (pintype "bidirectional"))
      (node (ref "X2") (pin "P$2") (pinfunction "P$2_P$2") (pintype "bidirectional"))
      (node (ref "Z1") (pin "2") (pinfunction "2_2") (pintype "passive"))
      (node (ref "Z2") (pin "2") (pinfunction "2_2") (pintype "passive"))
    )
    (net (code "51") (name "/VIN") (class "Default")
      (node (ref "D1") (pin "C") (pinfunction "C_C") (pintype "passive"))
      (node (ref "PC1") (pin "+") (pinfunction "+_+") (pintype "passive"))
      (node (ref "POWER") (pin "8") (pinfunction "8_8") (pintype "passive"))
      (node (ref "RN1") (pin "8") (pinfunction "2_8") (pintype "passive"))
      (node (ref "TP_VIN") (pin "X") (pinfunction "TESTP_X") (pintype "passive"))
      (node (ref "U1") (pin "3") (pinfunction "IN_3") (pintype "input"))
    )
    (net (code "52") (name "/XT1") (class "Default")
      (node (ref "C9") (pin "1") (pinfunction "1_1") (pintype "passive"))
      (node (ref "R1") (pin "1") (pinfunction "1_1") (pintype "passive"))
      (node (ref "TP_XT3") (pin "X") (pinfunction "TESTP_X") (pintype "passive"))
      (node (ref "U3") (pin "1") (pinfunction "XTAL1_1") (pintype "bidirectional"))
      (node (ref "Y1") (pin "2") (pinfunction "2_2") (pintype "passive"))
    )
    (net (code "53") (name "/XT2") (class "Default")
      (node (ref "C11") (pin "1") (pinfunction "1_1") (pintype "passive"))
      (node (ref "R1") (pin "2") (pinfunction "2_2") (pintype "passive"))
      (node (ref "TP_XT4") (pin "X") (pinfunction "TESTP_X") (pintype "passive"))
      (node (ref "U3") (pin "2") (pinfunction "XTAL2(PC0)_2") (pintype "bidirectional"))
      (node (ref "Y1") (pin "1") (pinfunction "1_1") (pintype "passive"))
    )
    (net (code "54") (name "/XTAL1") (class "Default")
      (node (ref "R2") (pin "1") (pinfunction "1_1") (pintype "passive"))
      (node (ref "TP_XT1") (pin "X") (pinfunction "TESTP_X") (pintype "passive"))
      (node (ref "Y2") (pin "3") (pinfunction "3_3") (pintype "passive"))
      (node (ref "ZU4") (pin "9") (pinfunction "XTAL1_9") (pintype "bidirectional"))
    )
    (net (code "55") (name "/XTAL2") (class "Default")
      (node (ref "R2") (pin "2") (pinfunction "2_2") (pintype "passive"))
      (node (ref "TP_XT2") (pin "X") (pinfunction "TESTP_X") (pintype "passive"))
      (node (ref "Y2") (pin "1") (pinfunction "1_1") (pintype "passive"))
      (node (ref "ZU4") (pin "10") (pinfunction "XTAL2_10") (pintype "bidirectional"))
    )
    (net (code "56") (name "/XUSB") (class "Default")
      (node (ref "F1") (pin "2") (pinfunction "2_2") (pintype "passive"))
      (node (ref "TP_XUSB") (pin "X") (pinfunction "TESTP_X") (pintype "passive"))
      (node (ref "X2") (pin "1") (pinfunction "1_1") (pintype "bidirectional"))
    )
    (net (code "57") (name "GND") (class "Default")
      (node (ref "C1") (pin "1") (pinfunction "1_1") (pintype "passive"))
      (node (ref "C10") (pin "1") (pinfunction "1_1") (pintype "passive"))
      (node (ref "C11") (pin "2") (pinfunction "2_2") (pintype "passive"))
      (node (ref "C2") (pin "1") (pinfunction "1_1") (pintype "passive"))
      (node (ref "C3") (pin "1") (pinfunction "1_1") (pintype "passive"))
      (node (ref "C4") (pin "1") (pinfunction "1_1") (pintype "passive"))
      (node (ref "C6") (pin "1") (pinfunction "1_1") (pintype "passive"))
      (node (ref "C7") (pin "2") (pinfunction "2_2") (pintype "passive"))
      (node (ref "C9") (pin "2") (pinfunction "2_2") (pintype "passive"))
      (node (ref "GROUND") (pin "1") (pinfunction "1_1") (pintype "passive"))
      (node (ref "ICSP") (pin "6") (pinfunction "6_6") (pintype "passive"))
      (node (ref "ICSP1") (pin "6") (pinfunction "6_6") (pintype "passive"))
      (node (ref "IOH") (pin "7") (pinfunction "7_7") (pintype "passive"))
      (node (ref "L") (pin "C") (pinfunction "C_C") (pintype "passive"))
      (node (ref "ON") (pin "C") (pinfunction "C_C") (pintype "passive"))
      (node (ref "PC1") (pin "-") (pinfunction "-_-") (pintype "passive"))
      (node (ref "PC2") (pin "-") (pinfunction "-_-") (pintype "passive"))
      (node (ref "POWER") (pin "6") (pinfunction "6_6") (pintype "passive"))
      (node (ref "POWER") (pin "7") (pinfunction "7_7") (pintype "passive"))
      (node (ref "RESET") (pin "1") (pinfunction "1_1") (pintype "passive"))
      (node (ref "RESET") (pin "2") (pinfunction "2_2") (pintype "passive"))
      (node (ref "RN1") (pin "7") (pinfunction "2_7") (pintype "passive"))
      (node (ref "RN2") (pin "5") (pinfunction "2_5") (pintype "passive"))
      (node (ref "U1") (pin "1") (pinfunction "GND/ADJ_1") (pintype "input"))
      (node (ref "U2") (pin "2") (pinfunction "GND_2") (pintype "power_in"))
      (node (ref "U3") (pin "3") (pinfunction "GND_3") (pintype "power_in"))
      (node (ref "U3") (pin "33") (pinfunction "PAD_33") (pintype "power_in"))
      (node (ref "U5") (pin "4") (pinfunction "V-_4") (pintype "power_in"))
      (node (ref "X1") (pin "1") (pinfunction "1_1") (pintype "power_in"))
      (node (ref "X1") (pin "3") (pinfunction "3_3") (pintype "power_in"))
      (node (ref "Y2") (pin "2") (pinfunction "2_2") (pintype "passive"))
      (node (ref "ZU4") (pin "22") (pinfunction "AGND_22") (pintype "power_in"))
      (node (ref "ZU4") (pin "8") (pinfunction "GND_8") (pintype "power_in"))
    )
    (net (code "58") (name "Net-(RN2B-2)") (class "Default")
      (node (ref "RN2") (pin "7") (pinfunction "2_7") (pintype "passive"))
      (node (ref "RX") (pin "A") (pinfunction "A_A") (pintype "passive"))
      (node (ref "TP_RXL") (pin "X") (pinfunction "TESTP_X") (pintype "passive"))
    )
    (net (code "59") (name "Net-(RN2C-2)") (class "Default")
      (node (ref "RN2") (pin "6") (pinfunction "2_6") (pintype "passive"))
      (node (ref "TP_TXL") (pin "X") (pinfunction "TESTP_X") (pintype "passive"))
      (node (ref "TX") (pin "A") (pinfunction "A_A") (pintype "passive"))
    )
    (net (code "60") (name "Net-(RN4C-2)") (class "Default")
      (node (ref "ON") (pin "A") (pinfunction "A_A") (pintype "passive"))
      (node (ref "RN4") (pin "5") (pinfunction "2_5") (pintype "passive"))
      (node (ref "RN4") (pin "6") (pinfunction "2_6") (pintype "passive"))
      (node (ref "TP_ONL") (pin "X") (pinfunction "TESTP_X") (pintype "passive"))
    )
    (net (code "61") (name "Net-(TP_LL-TESTP)") (class "Default")
      (node (ref "L") (pin "A") (pinfunction "A_A") (pintype "passive"))
      (node (ref "RN2") (pin "1") (pinfunction "1_1") (pintype "passive"))
      (node (ref "TP_LL") (pin "X") (pinfunction "TESTP_X") (pintype "passive"))
    )
    (net (code "62") (name "Net-(TP_USBVCC-TESTP)") (class "Default")
      (node (ref "TP_USBVCC") (pin "X") (pinfunction "TESTP_X") (pintype "passive"))
      (node (ref "U3") (pin "31") (pinfunction "UVCC_31") (pintype "power_in"))
    )
    (net (code "63") (name "unconnected-(ORIGIN-TESTP-PadX)") (class "Default")
      (node (ref "ORIGIN") (pin "X") (pinfunction "TESTP_X") (pintype "passive"))
    )
    (net (code "64") (name "unconnected-(POWER-Pad1)") (class "Default")
      (node (ref "POWER") (pin "1") (pinfunction "1_1") (pintype "passive"))
    )
    (net (code "65") (name "unconnected-(RESET-5-GND-Pad5)") (class "Default")
      (node (ref "RESET") (pin "5") (pinfunction "5-GND_5") (pintype "power_in"))
    )
    (net (code "66") (name "unconnected-(RN3B-1-Pad2)") (class "Default")
      (node (ref "RN3") (pin "2") (pinfunction "1_2") (pintype "passive"))
    )
    (net (code "67") (name "unconnected-(RN3B-2-Pad7)") (class "Default")
      (node (ref "RN3") (pin "7") (pinfunction "2_7") (pintype "passive"))
    )
    (net (code "68") (name "unconnected-(RN3C-1-Pad3)") (class "Default")
      (node (ref "RN3") (pin "3") (pinfunction "1_3") (pintype "passive"))
    )
    (net (code "69") (name "unconnected-(RN3C-2-Pad6)") (class "Default")
      (node (ref "RN3") (pin "6") (pinfunction "2_6") (pintype "passive"))
    )
    (net (code "70") (name "unconnected-(U2-NC{slash}FB-Pad4)") (class "Default")
      (node (ref "U2") (pin "4") (pinfunction "NC/FB_4") (pintype "passive"))
    )
    (net (code "71") (name "unconnected-(U3-(AIN0{slash}INT1)PD1-Pad7)") (class "Default")
      (node (ref "U3") (pin "7") (pinfunction "(AIN0/INT1)PD1_7") (pintype "bidirectional"))
    )
    (net (code "72") (name "unconnected-(U3-(AIN2{slash}PCINT11)PC2-Pad5)") (class "Default")
      (node (ref "U3") (pin "5") (pinfunction "(AIN2/PCINT11)PC2_5") (pintype "bidirectional"))
    )
    (net (code "73") (name "unconnected-(U3-(INT4{slash}ICP1{slash}CLK0)PC7-Pad22)") (class "Default")
      (node (ref "U3") (pin "22") (pinfunction "(INT4/ICP1/CLK0)PC7_22") (pintype "bidirectional"))
    )
    (net (code "74") (name "unconnected-(U3-(OC0B{slash}INT0)PD0-Pad6)") (class "Default")
      (node (ref "U3") (pin "6") (pinfunction "(OC0B/INT0)PD0_6") (pintype "bidirectional"))
    )
    (net (code "75") (name "unconnected-(U3-(OC1A{slash}PCINT8)PC6-Pad23)") (class "Default")
      (node (ref "U3") (pin "23") (pinfunction "(OC1A/PCINT8)PC6_23") (pintype "bidirectional"))
    )
    (net (code "76") (name "unconnected-(U3-(PCINT9{slash}OC1B)PC5-Pad25)") (class "Default")
      (node (ref "U3") (pin "25") (pinfunction "(PCINT9/OC1B)PC5_25") (pintype "bidirectional"))
    )
    (net (code "77") (name "unconnected-(U3-(PCINT10)PC4-Pad26)") (class "Default")
      (node (ref "U3") (pin "26") (pinfunction "(PCINT10)PC4_26") (pintype "bidirectional"))
    )
    (net (code "78") (name "unconnected-(U3-(RTS{slash}AIN5{slash}INT6)PD6-Pad12)") (class "Default")
      (node (ref "U3") (pin "12") (pinfunction "(RTS/AIN5/INT6)PD6_12") (pintype "bidirectional"))
    )
    (net (code "79") (name "unconnected-(U3-(SS{slash}PCINT0)PB0-Pad14)") (class "Default")
      (node (ref "U3") (pin "14") (pinfunction "(SS/PCINT0)PB0_14") (pintype "bidirectional"))
    )
  )
)
